# OpenLabKostkaSchematPomiarowy1.net
KiCad netlist of a schematic drawn in EAGLE
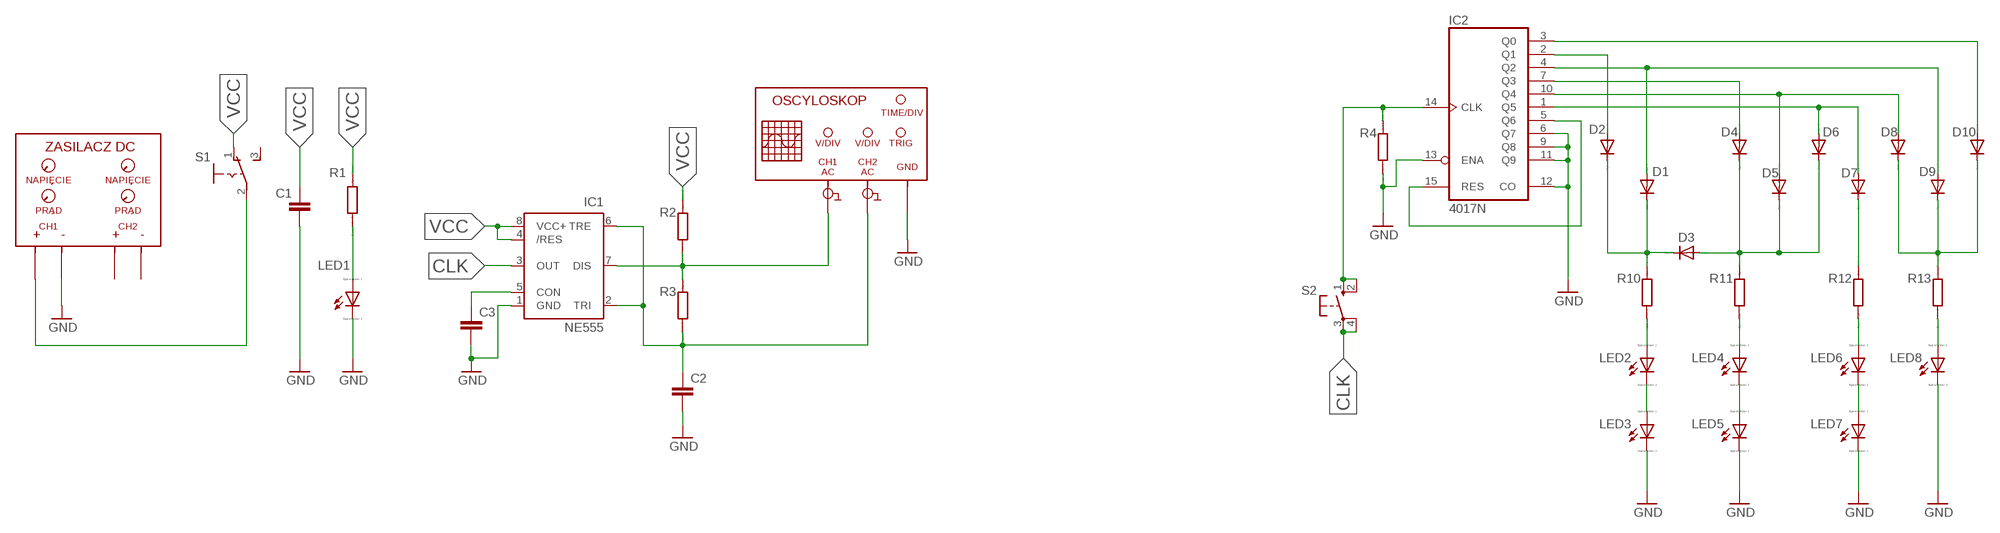
[diagram p0: schematic, sheet 1]

(export (version "E")
  (design (tool "Eeschema 10.0.6"))
  (components
    (comp (ref "C1")
      (value "C5/2.5")
      (footprint "eagle-import:C5B2.5")
      (libsource (lib "eagle-import") (part "C5/2.5"))
    )
    (comp (ref "C2")
      (value "C5/2.5")
      (footprint "eagle-import:C5B2.5")
      (libsource (lib "eagle-import") (part "C5/2.5"))
    )
    (comp (ref "C3")
      (value "C5/2.5")
      (footprint "eagle-import:C5B2.5")
      (libsource (lib "eagle-import") (part "C5/2.5"))
    )
    (comp (ref "D1")
      (value "1N4446")
      (footprint "eagle-import:DO35-10")
      (libsource (lib "eagle-import") (part "1N4446"))
    )
    (comp (ref "D2")
      (value "1N4446")
      (footprint "eagle-import:DO35-10")
      (libsource (lib "eagle-import") (part "1N4446"))
    )
    (comp (ref "D3")
      (value "1N4446")
      (footprint "eagle-import:DO35-10")
      (libsource (lib "eagle-import") (part "1N4446"))
    )
    (comp (ref "D4")
      (value "1N4446")
      (footprint "eagle-import:DO35-10")
      (libsource (lib "eagle-import") (part "1N4446"))
    )
    (comp (ref "D5")
      (value "1N4446")
      (footprint "eagle-import:DO35-10")
      (libsource (lib "eagle-import") (part "1N4446"))
    )
    (comp (ref "D6")
      (value "1N4446")
      (footprint "eagle-import:DO35-10")
      (libsource (lib "eagle-import") (part "1N4446"))
    )
    (comp (ref "D7")
      (value "1N4446")
      (footprint "eagle-import:DO35-10")
      (libsource (lib "eagle-import") (part "1N4446"))
    )
    (comp (ref "D8")
      (value "1N4446")
      (footprint "eagle-import:DO35-10")
      (libsource (lib "eagle-import") (part "1N4446"))
    )
    (comp (ref "D9")
      (value "1N4446")
      (footprint "eagle-import:DO35-10")
      (libsource (lib "eagle-import") (part "1N4446"))
    )
    (comp (ref "D10")
      (value "1N4446")
      (footprint "eagle-import:DO35-10")
      (libsource (lib "eagle-import") (part "1N4446"))
    )
    (comp (ref "IC1")
      (value "NE555")
      (footprint "eagle-import:DIL-08")
      (fields (field (name "MF") "Arrow Electronics") (field (name "MPN") "NE555N"))
      (libsource (lib "eagle-import") (part "NE555"))
    )
    (comp (ref "IC2")
      (value "4017N")
      (footprint "eagle-import:DIL16")
      (libsource (lib "eagle-import") (part "4017N"))
    )
    (comp (ref "LED1")
      (value "LED_ELD260")
      (footprint "eagle-import:LED_LD260")
      (libsource (lib "eagle-import") (part "LED_ELD260"))
    )
    (comp (ref "LED2")
      (value "LED_ELD260")
      (footprint "eagle-import:LED_LD260")
      (libsource (lib "eagle-import") (part "LED_ELD260"))
    )
    (comp (ref "LED3")
      (value "LED_ELD260")
      (footprint "eagle-import:LED_LD260")
      (libsource (lib "eagle-import") (part "LED_ELD260"))
    )
    (comp (ref "LED4")
      (value "LED_ELD260")
      (footprint "eagle-import:LED_LD260")
      (libsource (lib "eagle-import") (part "LED_ELD260"))
    )
    (comp (ref "LED5")
      (value "LED_ELD260")
      (footprint "eagle-import:LED_LD260")
      (libsource (lib "eagle-import") (part "LED_ELD260"))
    )
    (comp (ref "LED6")
      (value "LED_ELD260")
      (footprint "eagle-import:LED_LD260")
      (libsource (lib "eagle-import") (part "LED_ELD260"))
    )
    (comp (ref "LED7")
      (value "LED_ELD260")
      (footprint "eagle-import:LED_LD260")
      (libsource (lib "eagle-import") (part "LED_ELD260"))
    )
    (comp (ref "LED8")
      (value "LED_ELD260")
      (footprint "eagle-import:LED_LD260")
      (libsource (lib "eagle-import") (part "LED_ELD260"))
    )
    (comp (ref "R1")
      (value "R0204/7")
      (footprint "eagle-import:0204_7")
      (libsource (lib "eagle-import") (part "R0204/7"))
    )
    (comp (ref "R2")
      (value "R0204/7")
      (footprint "eagle-import:0204_7")
      (libsource (lib "eagle-import") (part "R0204/7"))
    )
    (comp (ref "R3")
      (value "R0204/7")
      (footprint "eagle-import:0204_7")
      (libsource (lib "eagle-import") (part "R0204/7"))
    )
    (comp (ref "R4")
      (value "R0204/7")
      (footprint "eagle-import:0204_7")
      (libsource (lib "eagle-import") (part "R0204/7"))
    )
    (comp (ref "R10")
      (value "R0204/7")
      (footprint "eagle-import:0204_7")
      (libsource (lib "eagle-import") (part "R0204/7"))
    )
    (comp (ref "R11")
      (value "R0204/7")
      (footprint "eagle-import:0204_7")
      (libsource (lib "eagle-import") (part "R0204/7"))
    )
    (comp (ref "R12")
      (value "R0204/7")
      (footprint "eagle-import:0204_7")
      (libsource (lib "eagle-import") (part "R0204/7"))
    )
    (comp (ref "R13")
      (value "R0204/7")
      (footprint "eagle-import:0204_7")
      (libsource (lib "eagle-import") (part "R0204/7"))
    )
    (comp (ref "S1")
      (value "255SB")
      (footprint "eagle-import:255SB")
      (libsource (lib "eagle-import") (part "255SB"))
    )
    (comp (ref "S2")
      (value "10-XX")
      (footprint "eagle-import:B3F-10XX")
      (fields (field (name "MPN") "B3F-1000"))
      (libsource (lib "eagle-import") (part "10-XX"))
    )
    (comp (ref "U$1")
      (value "OSCYLOSKOP_AC_AC")
      (footprint "eagle-import:OSCYLOSKOP")
      (libsource (lib "eagle-import") (part "OSCYLOSKOP_AC_AC"))
    )
    (comp (ref "U$2")
      (value "ZASILACZ")
      (footprint "eagle-import:ZASILACZ")
      (libsource (lib "eagle-import") (part "ZASILACZ"))
    )
  )
  (nets
    (net (code "1") (name "CLK") (class "Default")
      (node (ref "IC1") (pin "3") (pinfunction "OUT_3") (pintype "output"))
      (node (ref "S2") (pin "3") (pinfunction "P_3") (pintype "passive"))
      (node (ref "S2") (pin "4") (pinfunction "P1_4") (pintype "passive"))
    )
    (net (code "2") (name "GND") (class "Default")
      (node (ref "C1") (pin "1") (pinfunction "1_1") (pintype "passive"))
      (node (ref "C2") (pin "2") (pinfunction "2_2") (pintype "passive"))
      (node (ref "C3") (pin "2") (pinfunction "2_2") (pintype "passive"))
      (node (ref "IC1") (pin "1") (pinfunction "GND_1") (pintype "power_in"))
      (node (ref "IC2") (pin "11") (pinfunction "Q9_11") (pintype "output"))
      (node (ref "IC2") (pin "12") (pinfunction "CO_12") (pintype "output"))
      (node (ref "IC2") (pin "13") (pinfunction "ENA_13") (pintype "input"))
      (node (ref "IC2") (pin "6") (pinfunction "Q7_6") (pintype "output"))
      (node (ref "IC2") (pin "9") (pinfunction "Q8_9") (pintype "output"))
      (node (ref "LED1") (pin "K") (pinfunction "C_K") (pintype "passive"))
      (node (ref "LED3") (pin "K") (pinfunction "C_K") (pintype "passive"))
      (node (ref "LED5") (pin "K") (pinfunction "C_K") (pintype "passive"))
      (node (ref "LED7") (pin "K") (pinfunction "C_K") (pintype "passive"))
      (node (ref "LED8") (pin "K") (pinfunction "C_K") (pintype "passive"))
      (node (ref "R4") (pin "1") (pinfunction "1_1") (pintype "passive"))
      (node (ref "U$1") (pin "GND") (pinfunction "GND_GND") (pintype "bidirectional"))
      (node (ref "U$2") (pin "C1-") (pinfunction "CH1-_C1-") (pintype "bidirectional"))
    )
    (net (code "3") (name "Net-(D1-PadC)") (class "Default")
      (node (ref "D1") (pin "C") (pinfunction "C_C") (pintype "passive"))
      (node (ref "D2") (pin "C") (pinfunction "C_C") (pintype "passive"))
      (node (ref "D3") (pin "C") (pinfunction "C_C") (pintype "passive"))
      (node (ref "R10") (pin "2") (pinfunction "2_2") (pintype "passive"))
    )
    (net (code "4") (name "Net-(D3-PadA)") (class "Default")
      (node (ref "D3") (pin "A") (pinfunction "A_A") (pintype "passive"))
      (node (ref "D4") (pin "C") (pinfunction "C_C") (pintype "passive"))
      (node (ref "D5") (pin "C") (pinfunction "C_C") (pintype "passive"))
      (node (ref "D6") (pin "C") (pinfunction "C_C") (pintype "passive"))
      (node (ref "R11") (pin "2") (pinfunction "2_2") (pintype "passive"))
    )
    (net (code "5") (name "Net-(D7-PadC)") (class "Default")
      (node (ref "D7") (pin "C") (pinfunction "C_C") (pintype "passive"))
      (node (ref "R12") (pin "2") (pinfunction "2_2") (pintype "passive"))
    )
    (net (code "6") (name "Net-(D10-PadC)") (class "Default")
      (node (ref "D10") (pin "C") (pinfunction "C_C") (pintype "passive"))
      (node (ref "D8") (pin "C") (pinfunction "C_C") (pintype "passive"))
      (node (ref "D9") (pin "C") (pinfunction "C_C") (pintype "passive"))
      (node (ref "R13") (pin "2") (pinfunction "2_2") (pintype "passive"))
    )
    (net (code "7") (name "Net-(IC1-CON)") (class "Default")
      (node (ref "C3") (pin "1") (pinfunction "1_1") (pintype "passive"))
      (node (ref "IC1") (pin "5") (pinfunction "CON_5") (pintype "input"))
    )
    (net (code "8") (name "Net-(IC1-DIS)") (class "Default")
      (node (ref "IC1") (pin "7") (pinfunction "DIS_7") (pintype "input"))
      (node (ref "R2") (pin "1") (pinfunction "1_1") (pintype "passive"))
      (node (ref "R3") (pin "2") (pinfunction "2_2") (pintype "passive"))
      (node (ref "U$1") (pin "CH1") (pinfunction "CH1_CH1") (pintype "bidirectional"))
    )
    (net (code "9") (name "Net-(IC1-TRE)") (class "Default")
      (node (ref "C2") (pin "1") (pinfunction "1_1") (pintype "passive"))
      (node (ref "IC1") (pin "2") (pinfunction "TRI_2") (pintype "input"))
      (node (ref "IC1") (pin "6") (pinfunction "TRE_6") (pintype "input"))
      (node (ref "R3") (pin "1") (pinfunction "1_1") (pintype "passive"))
      (node (ref "U$1") (pin "CH2") (pinfunction "CH2_CH2") (pintype "bidirectional"))
    )
    (net (code "10") (name "Net-(IC2A-CLK)") (class "Default")
      (node (ref "IC2") (pin "14") (pinfunction "CLK_14") (pintype "input"))
      (node (ref "R4") (pin "2") (pinfunction "2_2") (pintype "passive"))
      (node (ref "S2") (pin "1") (pinfunction "S_1") (pintype "passive"))
      (node (ref "S2") (pin "2") (pinfunction "S1_2") (pintype "passive"))
    )
    (net (code "11") (name "Net-(IC2A-Q0)") (class "Default")
      (node (ref "D10") (pin "A") (pinfunction "A_A") (pintype "passive"))
      (node (ref "IC2") (pin "3") (pinfunction "Q0_3") (pintype "output"))
    )
    (net (code "12") (name "Net-(IC2A-Q1)") (class "Default")
      (node (ref "D2") (pin "A") (pinfunction "A_A") (pintype "passive"))
      (node (ref "IC2") (pin "2") (pinfunction "Q1_2") (pintype "output"))
    )
    (net (code "13") (name "Net-(IC2A-Q2)") (class "Default")
      (node (ref "D1") (pin "A") (pinfunction "A_A") (pintype "passive"))
      (node (ref "D9") (pin "A") (pinfunction "A_A") (pintype "passive"))
      (node (ref "IC2") (pin "4") (pinfunction "Q2_4") (pintype "output"))
    )
    (net (code "14") (name "Net-(IC2A-Q3)") (class "Default")
      (node (ref "D4") (pin "A") (pinfunction "A_A") (pintype "passive"))
      (node (ref "IC2") (pin "7") (pinfunction "Q3_7") (pintype "output"))
    )
    (net (code "15") (name "Net-(IC2A-Q4)") (class "Default")
      (node (ref "D5") (pin "A") (pinfunction "A_A") (pintype "passive"))
      (node (ref "D8") (pin "A") (pinfunction "A_A") (pintype "passive"))
      (node (ref "IC2") (pin "10") (pinfunction "Q4_10") (pintype "output"))
    )
    (net (code "16") (name "Net-(IC2A-Q5)") (class "Default")
      (node (ref "D6") (pin "A") (pinfunction "A_A") (pintype "passive"))
      (node (ref "D7") (pin "A") (pinfunction "A_A") (pintype "passive"))
      (node (ref "IC2") (pin "1") (pinfunction "Q5_1") (pintype "output"))
    )
    (net (code "17") (name "Net-(IC2A-Q6)") (class "Default")
      (node (ref "IC2") (pin "15") (pinfunction "RES_15") (pintype "input"))
      (node (ref "IC2") (pin "5") (pinfunction "Q6_5") (pintype "output"))
    )
    (net (code "18") (name "Net-(LED1-PadA)") (class "Default")
      (node (ref "LED1") (pin "A") (pinfunction "A_A") (pintype "passive"))
      (node (ref "R1") (pin "1") (pinfunction "1_1") (pintype "passive"))
    )
    (net (code "19") (name "Net-(LED2-C)") (class "Default")
      (node (ref "LED2") (pin "K") (pinfunction "C_K") (pintype "passive"))
      (node (ref "LED3") (pin "A") (pinfunction "A_A") (pintype "passive"))
    )
    (net (code "20") (name "Net-(LED2-PadA)") (class "Default")
      (node (ref "LED2") (pin "A") (pinfunction "A_A") (pintype "passive"))
      (node (ref "R10") (pin "1") (pinfunction "1_1") (pintype "passive"))
    )
    (net (code "21") (name "Net-(LED4-C)") (class "Default")
      (node (ref "LED4") (pin "K") (pinfunction "C_K") (pintype "passive"))
      (node (ref "LED5") (pin "A") (pinfunction "A_A") (pintype "passive"))
    )
    (net (code "22") (name "Net-(LED4-PadA)") (class "Default")
      (node (ref "LED4") (pin "A") (pinfunction "A_A") (pintype "passive"))
      (node (ref "R11") (pin "1") (pinfunction "1_1") (pintype "passive"))
    )
    (net (code "23") (name "Net-(LED6-C)") (class "Default")
      (node (ref "LED6") (pin "K") (pinfunction "C_K") (pintype "passive"))
      (node (ref "LED7") (pin "A") (pinfunction "A_A") (pintype "passive"))
    )
    (net (code "24") (name "Net-(LED6-PadA)") (class "Default")
      (node (ref "LED6") (pin "A") (pinfunction "A_A") (pintype "passive"))
      (node (ref "R12") (pin "1") (pinfunction "1_1") (pintype "passive"))
    )
    (net (code "25") (name "Net-(LED8-PadA)") (class "Default")
      (node (ref "LED8") (pin "A") (pinfunction "A_A") (pintype "passive"))
      (node (ref "R13") (pin "1") (pinfunction "1_1") (pintype "passive"))
    )
    (net (code "26") (name "Net-(S1-P)") (class "Default")
      (node (ref "S1") (pin "2") (pinfunction "P_2") (pintype "passive"))
      (node (ref "U$2") (pin "C1+") (pinfunction "CH1+_C1+") (pintype "bidirectional"))
    )
    (net (code "27") (name "VCC") (class "Default")
      (node (ref "C1") (pin "2") (pinfunction "2_2") (pintype "passive"))
      (node (ref "IC1") (pin "4") (pinfunction "/RES_4") (pintype "input"))
      (node (ref "IC1") (pin "8") (pinfunction "VCC+_8") (pintype "power_in"))
      (node (ref "R1") (pin "2") (pinfunction "2_2") (pintype "passive"))
      (node (ref "R2") (pin "2") (pinfunction "2_2") (pintype "passive"))
      (node (ref "S1") (pin "1") (pinfunction "O_1") (pintype "passive"))
    )
    (net (code "28") (name "unconnected-(S1-S-Pad3)") (class "Default")
      (node (ref "S1") (pin "3") (pinfunction "S_3") (pintype "passive"))
    )
    (net (code "29") (name "unconnected-(U$2-CH2+-PadC2+)") (class "Default")
      (node (ref "U$2") (pin "C2+") (pinfunction "CH2+_C2+") (pintype "bidirectional"))
    )
    (net (code "30") (name "unconnected-(U$2-CH2--PadC2-)") (class "Default")
      (node (ref "U$2") (pin "C2-") (pinfunction "CH2-_C2-") (pintype "bidirectional"))
    )
  )
)
